# Schematic.net
KiCad netlist of a schematic drawn in Altium Designer
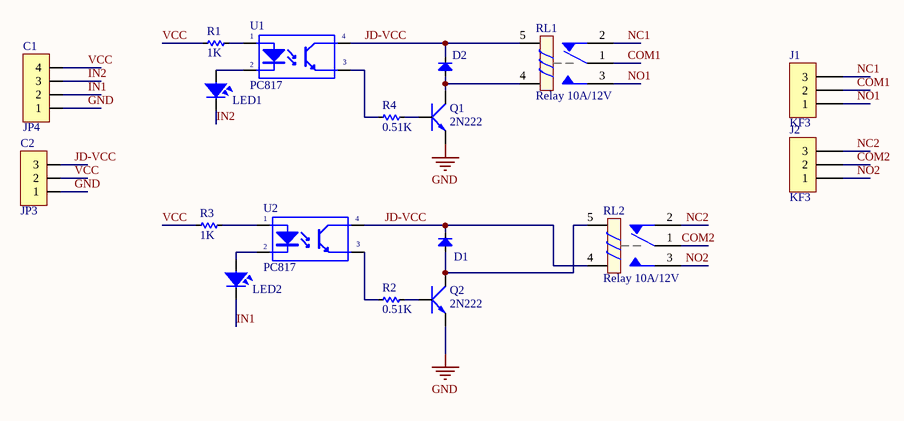
[diagram p0: Schematic.SchDoc]

(export (version "E")
  (design (tool "Eeschema 10.0.6"))
  (components
    (comp (ref "C1")
      (value "JP4")
      (footprint "JP4-C1T")
      (description "WR-PHD 2.54 mm Angled Socket Header")
      (fields
        (field (name "MANUFACTURER") "Würth Elektronik eiSos GmbH")
        (field (name "PARTNO") "613004143121")
        (field (name "CREATED BY") "Karrer Zheng")
      )
      (libsource (lib "LIBRARY") (part "JP4"))
    )
    (comp (ref "C2")
      (value "JP3")
      (footprint "JP3-D1T")
      (description "WR-PHD 2.54 mm Angled Socket Header")
      (fields
        (field (name "MANUFACTURER") "Würth Elektronik eiSos GmbH")
        (field (name "PARTNO") "613003143121")
        (field (name "CREATED BY") "Karrer Zheng")
      )
      (libsource (lib "LIBRARY") (part "JP3"))
    )
    (comp (ref "D1")
      (value "Diode SMD")
      (footprint "DIO-SMD-106")
      (description "Default Diode")
      (fields (field (name "PUBLISHER") "Altium Limited"))
      (libsource (lib "LIBRARY") (part "Diode SMD"))
    )
    (comp (ref "D2")
      (value "Diode SMD")
      (footprint "DIO-SMD-106")
      (description "Default Diode")
      (fields (field (name "PUBLISHER") "Altium Limited"))
      (libsource (lib "LIBRARY") (part "Diode SMD"))
    )
    (comp (ref "J1")
      (value "KF3")
      (footprint "KF3-3.5")
      (fields
        (field (name "MANUFACTURER") "Würth Elektronik eiSos GmbH")
        (field (name "PARTNO") "691103110003")
        (field (name "CREATED BY") "Karrer Zheng")
      )
      (libsource (lib "LIBRARY") (part "KF3"))
    )
    (comp (ref "J2")
      (value "KF3")
      (footprint "KF3-3.5")
      (fields
        (field (name "MANUFACTURER") "Würth Elektronik eiSos GmbH")
        (field (name "PARTNO") "691103110003")
        (field (name "CREATED BY") "Karrer Zheng")
      )
      (libsource (lib "LIBRARY") (part "KF3"))
    )
    (comp (ref "LED1") (value "LED") (footprint "LED-0805-Red") (libsource (lib "LIBRARY") (part "LED SMD")))
    (comp (ref "LED2") (value "LED") (footprint "LED-0805-Red") (libsource (lib "LIBRARY") (part "LED SMD")))
    (comp (ref "Q1")
      (value "2N222")
      (footprint "SOT23-231")
      (description "NPN 600mW, ECB")
      (libsource (lib "LIBRARY") (part "2N222"))
    )
    (comp (ref "Q2")
      (value "2N222")
      (footprint "SOT23-231")
      (description "NPN 600mW, ECB")
      (libsource (lib "LIBRARY") (part "2N222"))
    )
    (comp (ref "R1")
      (value "1K")
      (footprint "RES-SMD-0805")
      (description "Resistor")
      (fields
        (field (name "MANUFACTURER") "Generic Components")
        (field (name "PUBLISHER") "Altium Hobart Technology Centre")
      )
      (libsource (lib "LIBRARY") (part "Res-SMD"))
    )
    (comp (ref "R2")
      (value "0.51K")
      (footprint "RES-SMD-0805")
      (description "Resistor")
      (fields
        (field (name "MANUFACTURER") "Generic Components")
        (field (name "PUBLISHER") "Altium Hobart Technology Centre")
      )
      (libsource (lib "LIBRARY") (part "Res-SMD"))
    )
    (comp (ref "R3")
      (value "1K")
      (footprint "RES-SMD-0805")
      (description "Resistor")
      (fields
        (field (name "MANUFACTURER") "Generic Components")
        (field (name "PUBLISHER") "Altium Hobart Technology Centre")
      )
      (libsource (lib "LIBRARY") (part "Res-SMD"))
    )
    (comp (ref "R4")
      (value "0.51K")
      (footprint "RES-SMD-0805")
      (description "Resistor")
      (fields
        (field (name "MANUFACTURER") "Generic Components")
        (field (name "PUBLISHER") "Altium Hobart Technology Centre")
      )
      (libsource (lib "LIBRARY") (part "Res-SMD"))
    )
    (comp (ref "RL1")
      (value "Relay 10A/12V")
      (footprint "RL_T78")
      (description "Relay SPDT,10A - 12VDC 5 Pin")
      (libsource (lib "syhaunguyen") (part "Relay 1"))
    )
    (comp (ref "RL2")
      (value "Relay 10A/12V")
      (footprint "RL_T78")
      (description "Relay SPDT,10A - 12VDC 5 Pin")
      (libsource (lib "syhaunguyen") (part "Relay 1"))
    )
    (comp (ref "U1")
      (value "PC817")
      (footprint "DIP4")
      (description "Single Opto")
      (libsource (lib "LIBRARY") (part "PC817"))
    )
    (comp (ref "U2")
      (value "PC817")
      (footprint "DIP4")
      (description "Single Opto")
      (libsource (lib "LIBRARY") (part "PC817"))
    )
  )
  (nets
    (net (code "1") (name "/COM1") (class "Default")
      (node (ref "J1") (pin "2") (pinfunction "2_2") (pintype "passive"))
      (node (ref "RL1") (pin "1") (pinfunction "1_1") (pintype "passive"))
    )
    (net (code "2") (name "/COM2") (class "Default")
      (node (ref "J2") (pin "2") (pinfunction "2_2") (pintype "passive"))
      (node (ref "RL2") (pin "1") (pinfunction "1_1") (pintype "passive"))
    )
    (net (code "3") (name "/IN1") (class "Default")
      (node (ref "C1") (pin "2") (pinfunction "2_2") (pintype "passive"))
      (node (ref "LED2") (pin "2") (pinfunction "2_2") (pintype "passive"))
    )
    (net (code "4") (name "/IN2") (class "Default")
      (node (ref "C1") (pin "3") (pinfunction "3_3") (pintype "passive"))
      (node (ref "LED1") (pin "2") (pinfunction "2_2") (pintype "passive"))
    )
    (net (code "5") (name "/JD-VCC") (class "Default")
      (node (ref "C2") (pin "3") (pinfunction "3_3") (pintype "passive"))
      (node (ref "D1") (pin "2") (pinfunction "K_2") (pintype "passive"))
      (node (ref "D2") (pin "2") (pinfunction "K_2") (pintype "passive"))
      (node (ref "RL1") (pin "5") (pinfunction "5_5") (pintype "passive"))
      (node (ref "RL2") (pin "4") (pinfunction "4_4") (pintype "passive"))
      (node (ref "U1") (pin "4") (pinfunction "C_4") (pintype "passive"))
      (node (ref "U2") (pin "4") (pinfunction "C_4") (pintype "passive"))
    )
    (net (code "6") (name "/NC1") (class "Default")
      (node (ref "J1") (pin "3") (pinfunction "3_3") (pintype "passive"))
      (node (ref "RL1") (pin "2") (pinfunction "2_2") (pintype "passive"))
    )
    (net (code "7") (name "/NC2") (class "Default")
      (node (ref "J2") (pin "3") (pinfunction "3_3") (pintype "passive"))
      (node (ref "RL2") (pin "2") (pinfunction "2_2") (pintype "passive"))
    )
    (net (code "8") (name "/NO1") (class "Default")
      (node (ref "J1") (pin "1") (pinfunction "1_1") (pintype "passive"))
      (node (ref "RL1") (pin "3") (pinfunction "3_3") (pintype "passive"))
    )
    (net (code "9") (name "/NO2") (class "Default")
      (node (ref "J2") (pin "1") (pinfunction "1_1") (pintype "passive"))
      (node (ref "RL2") (pin "3") (pinfunction "3_3") (pintype "passive"))
    )
    (net (code "10") (name "/VCC") (class "Default")
      (node (ref "C1") (pin "4") (pinfunction "4_4") (pintype "passive"))
      (node (ref "C2") (pin "2") (pinfunction "2_2") (pintype "passive"))
      (node (ref "R1") (pin "2") (pinfunction "2_2") (pintype "passive"))
      (node (ref "R3") (pin "2") (pinfunction "2_2") (pintype "passive"))
    )
    (net (code "11") (name "GND") (class "Default")
      (node (ref "C1") (pin "1") (pinfunction "1_1") (pintype "passive"))
      (node (ref "C2") (pin "1") (pinfunction "1_1") (pintype "passive"))
      (node (ref "Q1") (pin "1") (pinfunction "E_1") (pintype "passive"))
      (node (ref "Q2") (pin "1") (pinfunction "E_1") (pintype "passive"))
    )
    (net (code "12") (name "Net-(D1-A)") (class "Default")
      (node (ref "D1") (pin "1") (pinfunction "A_1") (pintype "passive"))
      (node (ref "Q2") (pin "3") (pinfunction "C_3") (pintype "passive"))
      (node (ref "RL2") (pin "5") (pinfunction "5_5") (pintype "passive"))
    )
    (net (code "13") (name "Net-(D2-A)") (class "Default")
      (node (ref "D2") (pin "1") (pinfunction "A_1") (pintype "passive"))
      (node (ref "Q1") (pin "3") (pinfunction "C_3") (pintype "passive"))
      (node (ref "RL1") (pin "4") (pinfunction "4_4") (pintype "passive"))
    )
    (net (code "14") (name "Net-(Q1-B)") (class "Default")
      (node (ref "Q1") (pin "2") (pinfunction "B_2") (pintype "passive"))
      (node (ref "R4") (pin "1") (pinfunction "1_1") (pintype "passive"))
    )
    (net (code "15") (name "Net-(Q2-B)") (class "Default")
      (node (ref "Q2") (pin "2") (pinfunction "B_2") (pintype "passive"))
      (node (ref "R2") (pin "1") (pinfunction "1_1") (pintype "passive"))
    )
    (net (code "16") (name "Net-(U1-A)") (class "Default")
      (node (ref "R1") (pin "1") (pinfunction "1_1") (pintype "passive"))
      (node (ref "U1") (pin "1") (pinfunction "A_1") (pintype "passive"))
    )
    (net (code "17") (name "Net-(U1-E)") (class "Default")
      (node (ref "R4") (pin "2") (pinfunction "2_2") (pintype "passive"))
      (node (ref "U1") (pin "3") (pinfunction "E_3") (pintype "passive"))
    )
    (net (code "18") (name "Net-(U1-K)") (class "Default")
      (node (ref "LED1") (pin "1") (pinfunction "1_1") (pintype "passive"))
      (node (ref "U1") (pin "2") (pinfunction "K_2") (pintype "passive"))
    )
    (net (code "19") (name "Net-(U2-A)") (class "Default")
      (node (ref "R3") (pin "1") (pinfunction "1_1") (pintype "passive"))
      (node (ref "U2") (pin "1") (pinfunction "A_1") (pintype "passive"))
    )
    (net (code "20") (name "Net-(U2-E)") (class "Default")
      (node (ref "R2") (pin "2") (pinfunction "2_2") (pintype "passive"))
      (node (ref "U2") (pin "3") (pinfunction "E_3") (pintype "passive"))
    )
    (net (code "21") (name "Net-(U2-K)") (class "Default")
      (node (ref "LED2") (pin "1") (pinfunction "1_1") (pintype "passive"))
      (node (ref "U2") (pin "2") (pinfunction "K_2") (pintype "passive"))
    )
  )
)
